# AMU-S08-V00-AMSIDCloops.net
KiCad netlist of a schematic drawn in Altium Designer
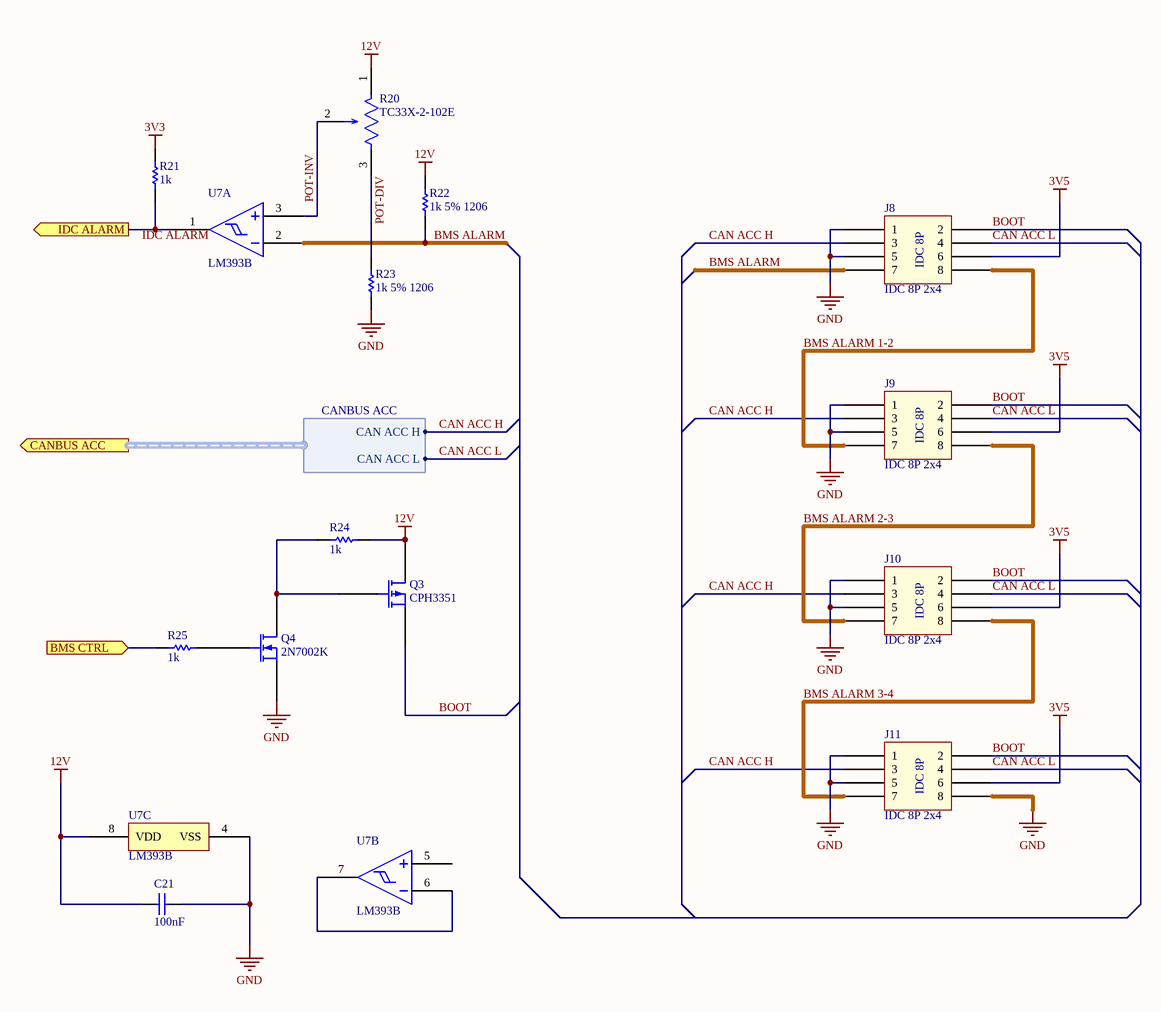
[diagram p0: AMU-S08-V00-AMSIDCloops.SchDoc]

(export (version "E")
  (design (tool "Eeschema 10.0.6"))
  (components
    (comp (ref "C21")
      (value "100nF")
      (footprint "Cap_Ceramic_0603")
      (description "Capacitor, Ceramic, SMD, 100nF, 50V, 5%, X7R, 0603")
      (libsource (lib "StandardCapacitors") (part "100nF 50V 5% X7R 0603"))
    )
    (comp (ref "J8")
      (value "IDC 8P 2x4")
      (footprint "IDC 2.54MM 8P")
      (libsource (lib "IDCConnectors") (part "IDC 8P 2x4"))
    )
    (comp (ref "J9")
      (value "IDC 8P 2x4")
      (footprint "IDC 2.54MM 8P")
      (libsource (lib "IDCConnectors") (part "IDC 8P 2x4"))
    )
    (comp (ref "J10")
      (value "IDC 8P 2x4")
      (footprint "IDC 2.54MM 8P")
      (libsource (lib "IDCConnectors") (part "IDC 8P 2x4"))
    )
    (comp (ref "J11")
      (value "IDC 8P 2x4")
      (footprint "IDC 2.54MM 8P")
      (libsource (lib "IDCConnectors") (part "IDC 8P 2x4"))
    )
    (comp (ref "Q3")
      (value "CPH3351")
      (footprint "SOT-23-3")
      (description "P-Channel 60V 1.8A (Ta) 1W (Ta) Surface Mount 3-CPH")
      (libsource (lib "QUTMS_Transistors") (part "CPH3351"))
    )
    (comp (ref "Q4")
      (value "2N7002K")
      (footprint "SOT-23-3")
      (description "N-Channel 60V 300mA (Ta) 350mW (Ta) Surface Mount SOT-23 (TO-236AB)")
      (libsource (lib "QUTMS_Transistors") (part "2N7002K"))
    )
    (comp (ref "R20")
      (value "TC33X-2-102E")
      (footprint "TC33")
      (description "1 kOhms 0.1W, 1/10W J Lead Surface Mount Trimmer Potentiometer Cermet 1 Turn Top Adjustment")
      (libsource (lib "QUTMS_TrimmerLibrary") (part "TC33X-2-102E"))
    )
    (comp (ref "R21")
      (value "1k")
      (footprint "Res_ThinFilm_0603")
      (description "Resistor, SMD, 1k, 0.1W, 5%, 0603")
      (libsource (lib "StandardResistors") (part "1k 5% 0603"))
    )
    (comp (ref "R22")
      (value "1k 5% 1206")
      (footprint "Res_ThinFilm_1206")
      (description "1 kOhms ±5% 0.25W, 1/4W Chip Resistor 1206 (3216 Metric) Moisture Resistant Thick Film")
      (libsource (lib "StandardResistors") (part "1k 5% 1206"))
    )
    (comp (ref "R23")
      (value "1k 5% 1206")
      (footprint "Res_ThinFilm_1206")
      (description "1 kOhms ±5% 0.25W, 1/4W Chip Resistor 1206 (3216 Metric) Moisture Resistant Thick Film")
      (libsource (lib "StandardResistors") (part "1k 5% 1206"))
    )
    (comp (ref "R24")
      (value "1k")
      (footprint "Res_ThinFilm_0603")
      (description "Resistor, SMD, 1k, 0.1W, 5%, 0603")
      (libsource (lib "StandardResistors") (part "1k 5% 0603"))
    )
    (comp (ref "R25")
      (value "1k")
      (footprint "Res_ThinFilm_1206")
      (description "1 kOhms ±5% 0.25W, 1/4W Chip Resistor 1206 (3216 Metric) Moisture Resistant Thick Film")
      (libsource (lib "StandardResistors") (part "1k 5% 1206"))
    )
    (comp (ref "U7")
      (value "LM393B")
      (footprint "SOIC-8")
      (description "Comparator General Purpose Open-Collector 8-SOIC")
      (libsource (lib "QUTMS_OpAmpLibrary") (part "LM393B"))
    )
  )
  (nets
    (net (code "3") (name "/BMS ALARM") (class "Default")
      (node (ref "J8") (pin "7") (pinfunction "7_7") (pintype "passive"))
      (node (ref "R22") (pin "1") (pinfunction "1_1") (pintype "passive"))
      (node (ref "U7") (pin "2") (pinfunction "IN1-_2") (pintype "passive"))
    )
    (net (code "4") (name "/BMS ALARM 1-2") (class "Default")
      (node (ref "J8") (pin "8") (pinfunction "8_8") (pintype "passive"))
      (node (ref "J9") (pin "7") (pinfunction "7_7") (pintype "passive"))
    )
    (net (code "5") (name "/BMS ALARM 2-3") (class "Default")
      (node (ref "J10") (pin "7") (pinfunction "7_7") (pintype "passive"))
      (node (ref "J9") (pin "8") (pinfunction "8_8") (pintype "passive"))
    )
    (net (code "6") (name "/BMS ALARM 3-4") (class "Default")
      (node (ref "J10") (pin "8") (pinfunction "8_8") (pintype "passive"))
      (node (ref "J11") (pin "7") (pinfunction "7_7") (pintype "passive"))
    )
    (net (code "7") (name "/BMS CTRL") (class "Default")
      (node (ref "R25") (pin "1") (pinfunction "1_1") (pintype "passive"))
    )
    (net (code "8") (name "/BOOT") (class "Default")
      (node (ref "J10") (pin "2") (pinfunction "2_2") (pintype "passive"))
      (node (ref "J11") (pin "2") (pinfunction "2_2") (pintype "passive"))
      (node (ref "J8") (pin "2") (pinfunction "2_2") (pintype "passive"))
      (node (ref "J9") (pin "2") (pinfunction "2_2") (pintype "passive"))
      (node (ref "Q3") (pin "S") (pinfunction "S_S") (pintype "passive"))
    )
    (net (code "9") (name "/CAN ACC H") (class "Default")
      (node (ref "J10") (pin "3") (pinfunction "3_3") (pintype "passive"))
      (node (ref "J11") (pin "3") (pinfunction "3_3") (pintype "passive"))
      (node (ref "J8") (pin "3") (pinfunction "3_3") (pintype "passive"))
      (node (ref "J9") (pin "3") (pinfunction "3_3") (pintype "passive"))
    )
    (net (code "10") (name "/CAN ACC L") (class "Default")
      (node (ref "J10") (pin "4") (pinfunction "4_4") (pintype "passive"))
      (node (ref "J11") (pin "4") (pinfunction "4_4") (pintype "passive"))
      (node (ref "J8") (pin "4") (pinfunction "4_4") (pintype "passive"))
      (node (ref "J9") (pin "4") (pinfunction "4_4") (pintype "passive"))
    )
    (net (code "11") (name "/IDC ALARM") (class "Default")
      (node (ref "R21") (pin "1") (pinfunction "1_1") (pintype "passive"))
      (node (ref "U7") (pin "1") (pinfunction "OUT1_1") (pintype "passive"))
    )
    (net (code "12") (name "/POT-DIV") (class "Default")
      (node (ref "R20") (pin "3") (pinfunction "3_3") (pintype "passive"))
      (node (ref "R23") (pin "2") (pinfunction "2_2") (pintype "passive"))
    )
    (net (code "13") (name "/POT-INV") (class "Default")
      (node (ref "R20") (pin "2") (pinfunction "2_2") (pintype "passive"))
      (node (ref "U7") (pin "3") (pinfunction "IN1+_3") (pintype "passive"))
    )
    (net (code "15") (name "3V3") (class "Default")
      (node (ref "R21") (pin "2") (pinfunction "2_2") (pintype "passive"))
    )
    (net (code "16") (name "3V5") (class "Default")
      (node (ref "J10") (pin "6") (pinfunction "6_6") (pintype "passive"))
      (node (ref "J11") (pin "6") (pinfunction "6_6") (pintype "passive"))
      (node (ref "J8") (pin "6") (pinfunction "6_6") (pintype "passive"))
      (node (ref "J9") (pin "6") (pinfunction "6_6") (pintype "passive"))
    )
    (net (code "17") (name "12V") (class "Default")
      (node (ref "C21") (pin "1") (pinfunction "1_1") (pintype "passive"))
      (node (ref "Q3") (pin "D") (pinfunction "D_D") (pintype "passive"))
      (node (ref "R20") (pin "1") (pinfunction "1_1") (pintype "passive"))
      (node (ref "R22") (pin "2") (pinfunction "2_2") (pintype "passive"))
      (node (ref "R24") (pin "2") (pinfunction "2_2") (pintype "passive"))
      (node (ref "U7") (pin "8") (pinfunction "VDD_8") (pintype "passive"))
    )
    (net (code "18") (name "GND") (class "Default")
      (node (ref "C21") (pin "2") (pinfunction "2_2") (pintype "passive"))
      (node (ref "J10") (pin "1") (pinfunction "1_1") (pintype "passive"))
      (node (ref "J10") (pin "5") (pinfunction "5_5") (pintype "passive"))
      (node (ref "J11") (pin "1") (pinfunction "1_1") (pintype "passive"))
      (node (ref "J11") (pin "5") (pinfunction "5_5") (pintype "passive"))
      (node (ref "J11") (pin "8") (pinfunction "8_8") (pintype "passive"))
      (node (ref "J8") (pin "1") (pinfunction "1_1") (pintype "passive"))
      (node (ref "J8") (pin "5") (pinfunction "5_5") (pintype "passive"))
      (node (ref "J9") (pin "1") (pinfunction "1_1") (pintype "passive"))
      (node (ref "J9") (pin "5") (pinfunction "5_5") (pintype "passive"))
      (node (ref "Q4") (pin "S") (pinfunction "S_S") (pintype "passive"))
      (node (ref "R23") (pin "1") (pinfunction "1_1") (pintype "passive"))
      (node (ref "U7") (pin "4") (pinfunction "VSS_4") (pintype "passive"))
    )
    (net (code "19") (name "Net-(Q3-PadG)") (class "Default")
      (node (ref "Q3") (pin "G") (pinfunction "G_G") (pintype "passive"))
      (node (ref "Q4") (pin "D") (pinfunction "D_D") (pintype "passive"))
      (node (ref "R24") (pin "1") (pinfunction "1_1") (pintype "passive"))
    )
    (net (code "20") (name "Net-(Q4-PadG)") (class "Default")
      (node (ref "Q4") (pin "G") (pinfunction "G_G") (pintype "passive"))
      (node (ref "R25") (pin "2") (pinfunction "2_2") (pintype "passive"))
    )
    (net (code "21") (name "Net-(U7B-IN2-)") (class "Default")
      (node (ref "U7") (pin "6") (pinfunction "IN2-_6") (pintype "passive"))
      (node (ref "U7") (pin "7") (pinfunction "OUT1_7") (pintype "passive"))
    )
    (net (code "22") (name "unconnected-(U7B-IN2+-Pad5)") (class "Default")
      (node (ref "U7") (pin "5") (pinfunction "IN2+_5") (pintype "passive"))
    )
  )
)
